# ToFnLED.net
KiCad netlist of a schematic drawn in EAGLE
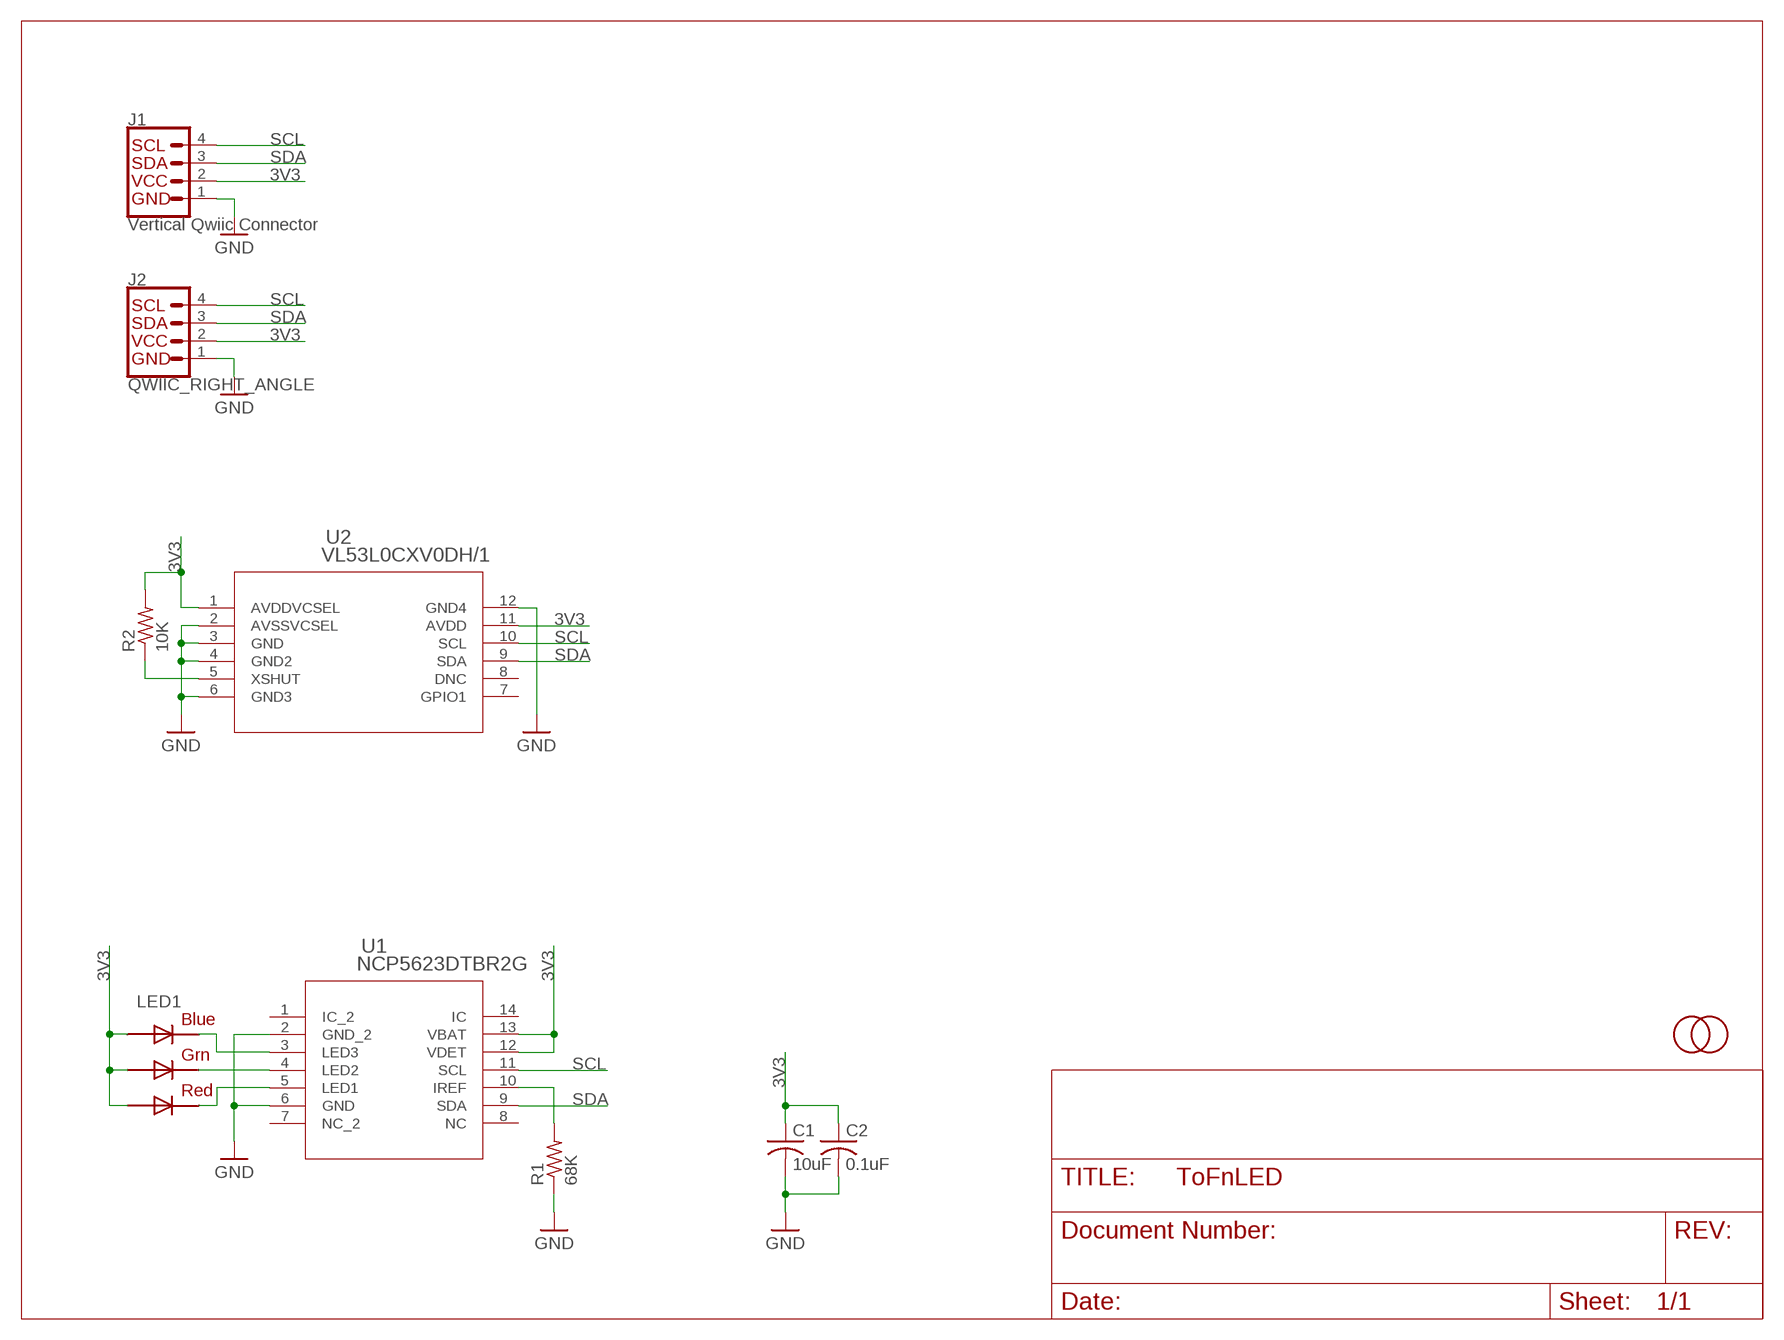
[diagram p0: schematic, sheet 1]

(export (version "E")
  (design (tool "Eeschema 10.0.6"))
  (components
    (comp (ref "C1")
      (value "10uF")
      (footprint "eagle-import:C0603")
      (libsource (lib "eagle-import") (part "C-USC0603"))
    )
    (comp (ref "C2")
      (value "0.1uF")
      (footprint "eagle-import:C0603")
      (libsource (lib "eagle-import") (part "C-USC0603"))
    )
    (comp (ref "J1")
      (value "Vertical Qwiic Connector")
      (footprint "eagle-import:JST04_1MM_VERT")
      (libsource (lib "eagle-import") (part "QWIIC_CONNECTOR"))
    )
    (comp (ref "J2")
      (value "QWIIC_RIGHT_ANGLE")
      (footprint "eagle-import:JST04_1MM_RA")
      (libsource (lib "eagle-import") (part "QWIIC_CONNECTORJS-1MM"))
    )
    (comp (ref "LED1")
      (value "RGBLED5050")
      (footprint "eagle-import:RGBLED5050")
      (libsource (lib "eagle-import") (part "RGBLED5050"))
    )
    (comp (ref "R1")
      (value "68K")
      (footprint "eagle-import:R0603")
      (libsource (lib "eagle-import") (part "R-US_R0603"))
    )
    (comp (ref "R2")
      (value "10K")
      (footprint "eagle-import:R0603")
      (libsource (lib "eagle-import") (part "R-US_R0603"))
    )
    (comp (ref "U$1")
      (value "FIDUCIAL")
      (footprint "eagle-import:FIDUCIAL_1MM")
      (libsource (lib "eagle-import") (part "FIDUCIAL"))
    )
    (comp (ref "U$2")
      (value "FIDUCIAL")
      (footprint "eagle-import:FIDUCIAL_1MM")
      (libsource (lib "eagle-import") (part "FIDUCIAL"))
    )
    (comp (ref "U1")
      (value "NCP5623DTBR2G")
      (footprint "eagle-import:TSSOP-14_ONS")
      (fields (field (name "COPYRIGHT") "Copyright (C) 2022 Ultra Librarian. All rights reserved."))
      (libsource (lib "eagle-import") (part "NCP5623DTBR2G"))
    )
    (comp (ref "U2")
      (value "VL53L0CXV0DH/1")
      (footprint "eagle-import:LGA12_STM")
      (fields (field (name "COPYRIGHT") "Copyright (C) 2022 Ultra Librarian. All rights reserved."))
      (libsource (lib "eagle-import") (part "VL53L0CXV0DH/1"))
    )
  )
  (nets
    (net (code "1") (name "/3V3") (class "Default")
      (node (ref "C1") (pin "1") (pinfunction "1_1") (pintype "passive"))
      (node (ref "C2") (pin "1") (pinfunction "1_1") (pintype "passive"))
      (node (ref "J1") (pin "2") (pinfunction "2_2") (pintype "power_in"))
      (node (ref "J2") (pin "2") (pinfunction "2_2") (pintype "power_in"))
      (node (ref "LED1") (pin "1") (pinfunction "GREEN_A_1") (pintype "bidirectional"))
      (node (ref "LED1") (pin "2") (pinfunction "RED_A_2") (pintype "bidirectional"))
      (node (ref "LED1") (pin "3") (pinfunction "BLUE_A_3") (pintype "bidirectional"))
      (node (ref "R2") (pin "2") (pinfunction "2_2") (pintype "passive"))
      (node (ref "U1") (pin "12") (pinfunction "VDET_12") (pintype "input"))
      (node (ref "U1") (pin "13") (pinfunction "VBAT_13") (pintype "power_in"))
      (node (ref "U2") (pin "1") (pinfunction "AVDDVCSEL_1") (pintype "power_in"))
      (node (ref "U2") (pin "11") (pinfunction "AVDD_11") (pintype "power_in"))
    )
    (net (code "2") (name "/SCL") (class "Default")
      (node (ref "J1") (pin "4") (pinfunction "4_4") (pintype "passive"))
      (node (ref "J2") (pin "4") (pinfunction "4_4") (pintype "passive"))
      (node (ref "U1") (pin "11") (pinfunction "SCL_11") (pintype "input"))
      (node (ref "U2") (pin "10") (pinfunction "SCL_10") (pintype "input"))
    )
    (net (code "3") (name "/SDA") (class "Default")
      (node (ref "J1") (pin "3") (pinfunction "3_3") (pintype "passive"))
      (node (ref "J2") (pin "3") (pinfunction "3_3") (pintype "passive"))
      (node (ref "U1") (pin "9") (pinfunction "SDA_9") (pintype "input"))
      (node (ref "U2") (pin "9") (pinfunction "SDA_9") (pintype "bidirectional"))
    )
    (net (code "4") (name "GND") (class "Default")
      (node (ref "C1") (pin "2") (pinfunction "2_2") (pintype "passive"))
      (node (ref "C2") (pin "2") (pinfunction "2_2") (pintype "passive"))
      (node (ref "J1") (pin "1") (pinfunction "1_1") (pintype "power_in"))
      (node (ref "J2") (pin "1") (pinfunction "1_1") (pintype "power_in"))
      (node (ref "R1") (pin "1") (pinfunction "1_1") (pintype "passive"))
      (node (ref "U1") (pin "2") (pinfunction "GND_2_2") (pintype "passive"))
      (node (ref "U1") (pin "6") (pinfunction "GND_6") (pintype "passive"))
      (node (ref "U2") (pin "12") (pinfunction "GND4_12") (pintype "power_in"))
      (node (ref "U2") (pin "2") (pinfunction "AVSSVCSEL_2") (pintype "power_in"))
      (node (ref "U2") (pin "3") (pinfunction "GND_3") (pintype "power_in"))
      (node (ref "U2") (pin "4") (pinfunction "GND2_4") (pintype "power_in"))
      (node (ref "U2") (pin "6") (pinfunction "GND3_6") (pintype "power_in"))
    )
    (net (code "5") (name "Net-(LED1-BLUE_C)") (class "Default")
      (node (ref "LED1") (pin "4") (pinfunction "BLUE_C_4") (pintype "bidirectional"))
      (node (ref "U1") (pin "3") (pinfunction "LED3_3") (pintype "output"))
    )
    (net (code "6") (name "Net-(LED1-GREEN_C)") (class "Default")
      (node (ref "LED1") (pin "6") (pinfunction "GREEN_C_6") (pintype "bidirectional"))
      (node (ref "U1") (pin "4") (pinfunction "LED2_4") (pintype "output"))
    )
    (net (code "7") (name "Net-(LED1-RED_C)") (class "Default")
      (node (ref "LED1") (pin "5") (pinfunction "RED_C_5") (pintype "bidirectional"))
      (node (ref "U1") (pin "5") (pinfunction "LED1_5") (pintype "output"))
    )
    (net (code "8") (name "Net-(U1-IREF)") (class "Default")
      (node (ref "R1") (pin "2") (pinfunction "2_2") (pintype "passive"))
      (node (ref "U1") (pin "10") (pinfunction "IREF_10") (pintype "passive"))
    )
    (net (code "9") (name "Net-(U2-XSHUT)") (class "Default")
      (node (ref "R2") (pin "1") (pinfunction "1_1") (pintype "passive"))
      (node (ref "U2") (pin "5") (pinfunction "XSHUT_5") (pintype "input"))
    )
    (net (code "10") (name "unconnected-(U1-IC-Pad14)") (class "Default")
      (node (ref "U1") (pin "14") (pinfunction "IC_14") (pintype "passive"))
    )
    (net (code "11") (name "unconnected-(U1-IC_2-Pad1)") (class "Default")
      (node (ref "U1") (pin "1") (pinfunction "IC_2_1") (pintype "passive"))
    )
    (net (code "12") (name "unconnected-(U1-NC-Pad8)") (class "Default")
      (node (ref "U1") (pin "8") (pinfunction "NC_8") (pintype "no_connect"))
    )
    (net (code "13") (name "unconnected-(U1-NC_2-Pad7)") (class "Default")
      (node (ref "U1") (pin "7") (pinfunction "NC_2_7") (pintype "no_connect"))
    )
    (net (code "14") (name "unconnected-(U2-DNC-Pad8)") (class "Default")
      (node (ref "U2") (pin "8") (pinfunction "DNC_8") (pintype "no_connect"))
    )
    (net (code "15") (name "unconnected-(U2-GPIO1-Pad7)") (class "Default")
      (node (ref "U2") (pin "7") (pinfunction "GPIO1_7") (pintype "bidirectional"))
    )
  )
)
